# harp_syringe_pump_v1_1.net
KiCad netlist of a schematic drawn in EAGLE
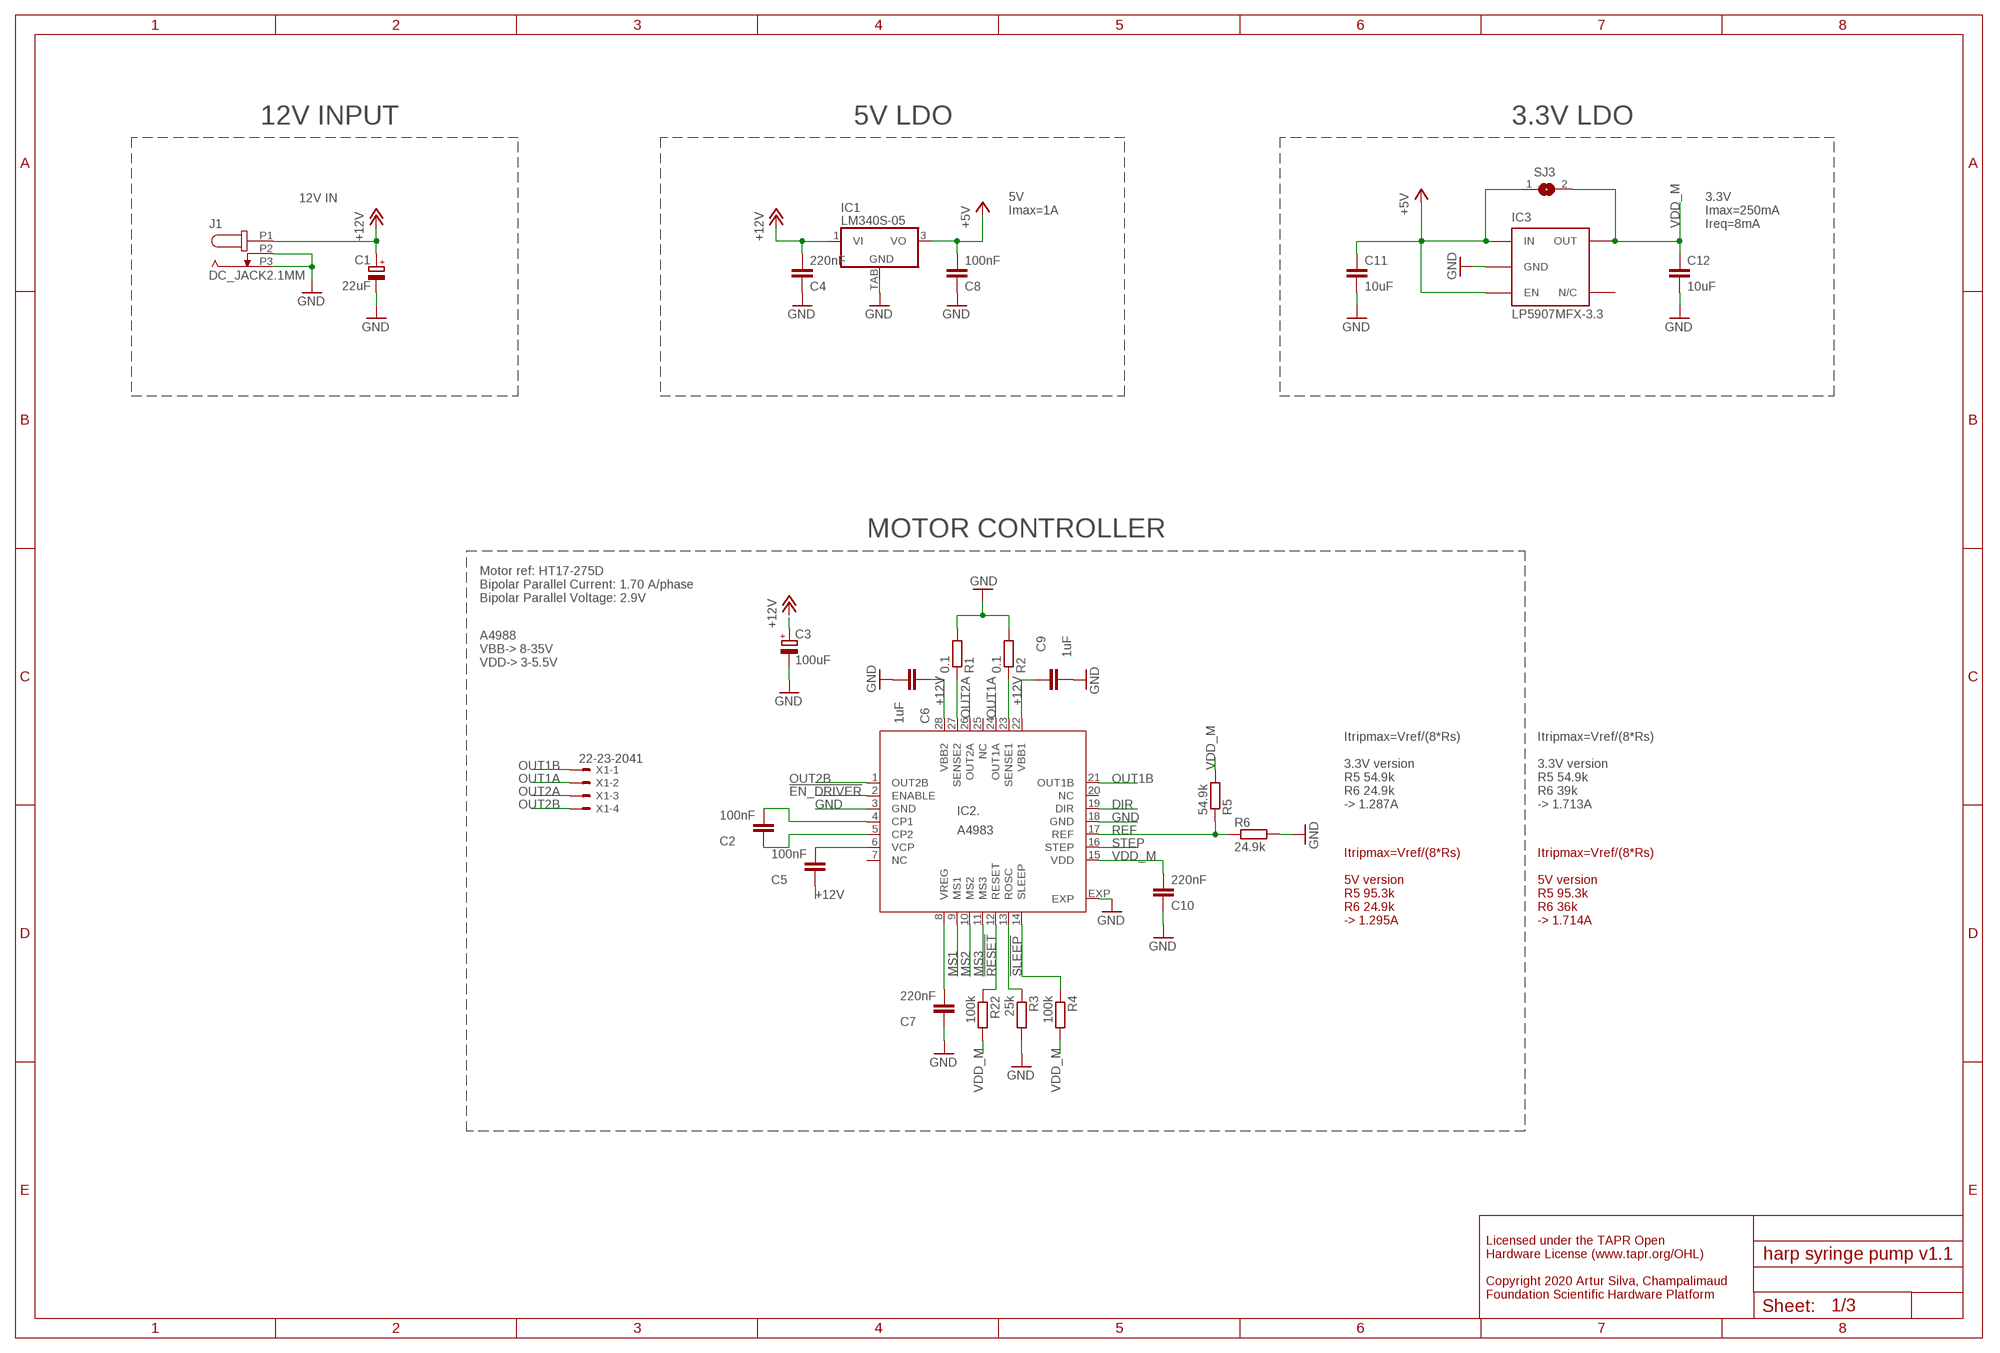
[diagram p0: schematic, sheet 1]
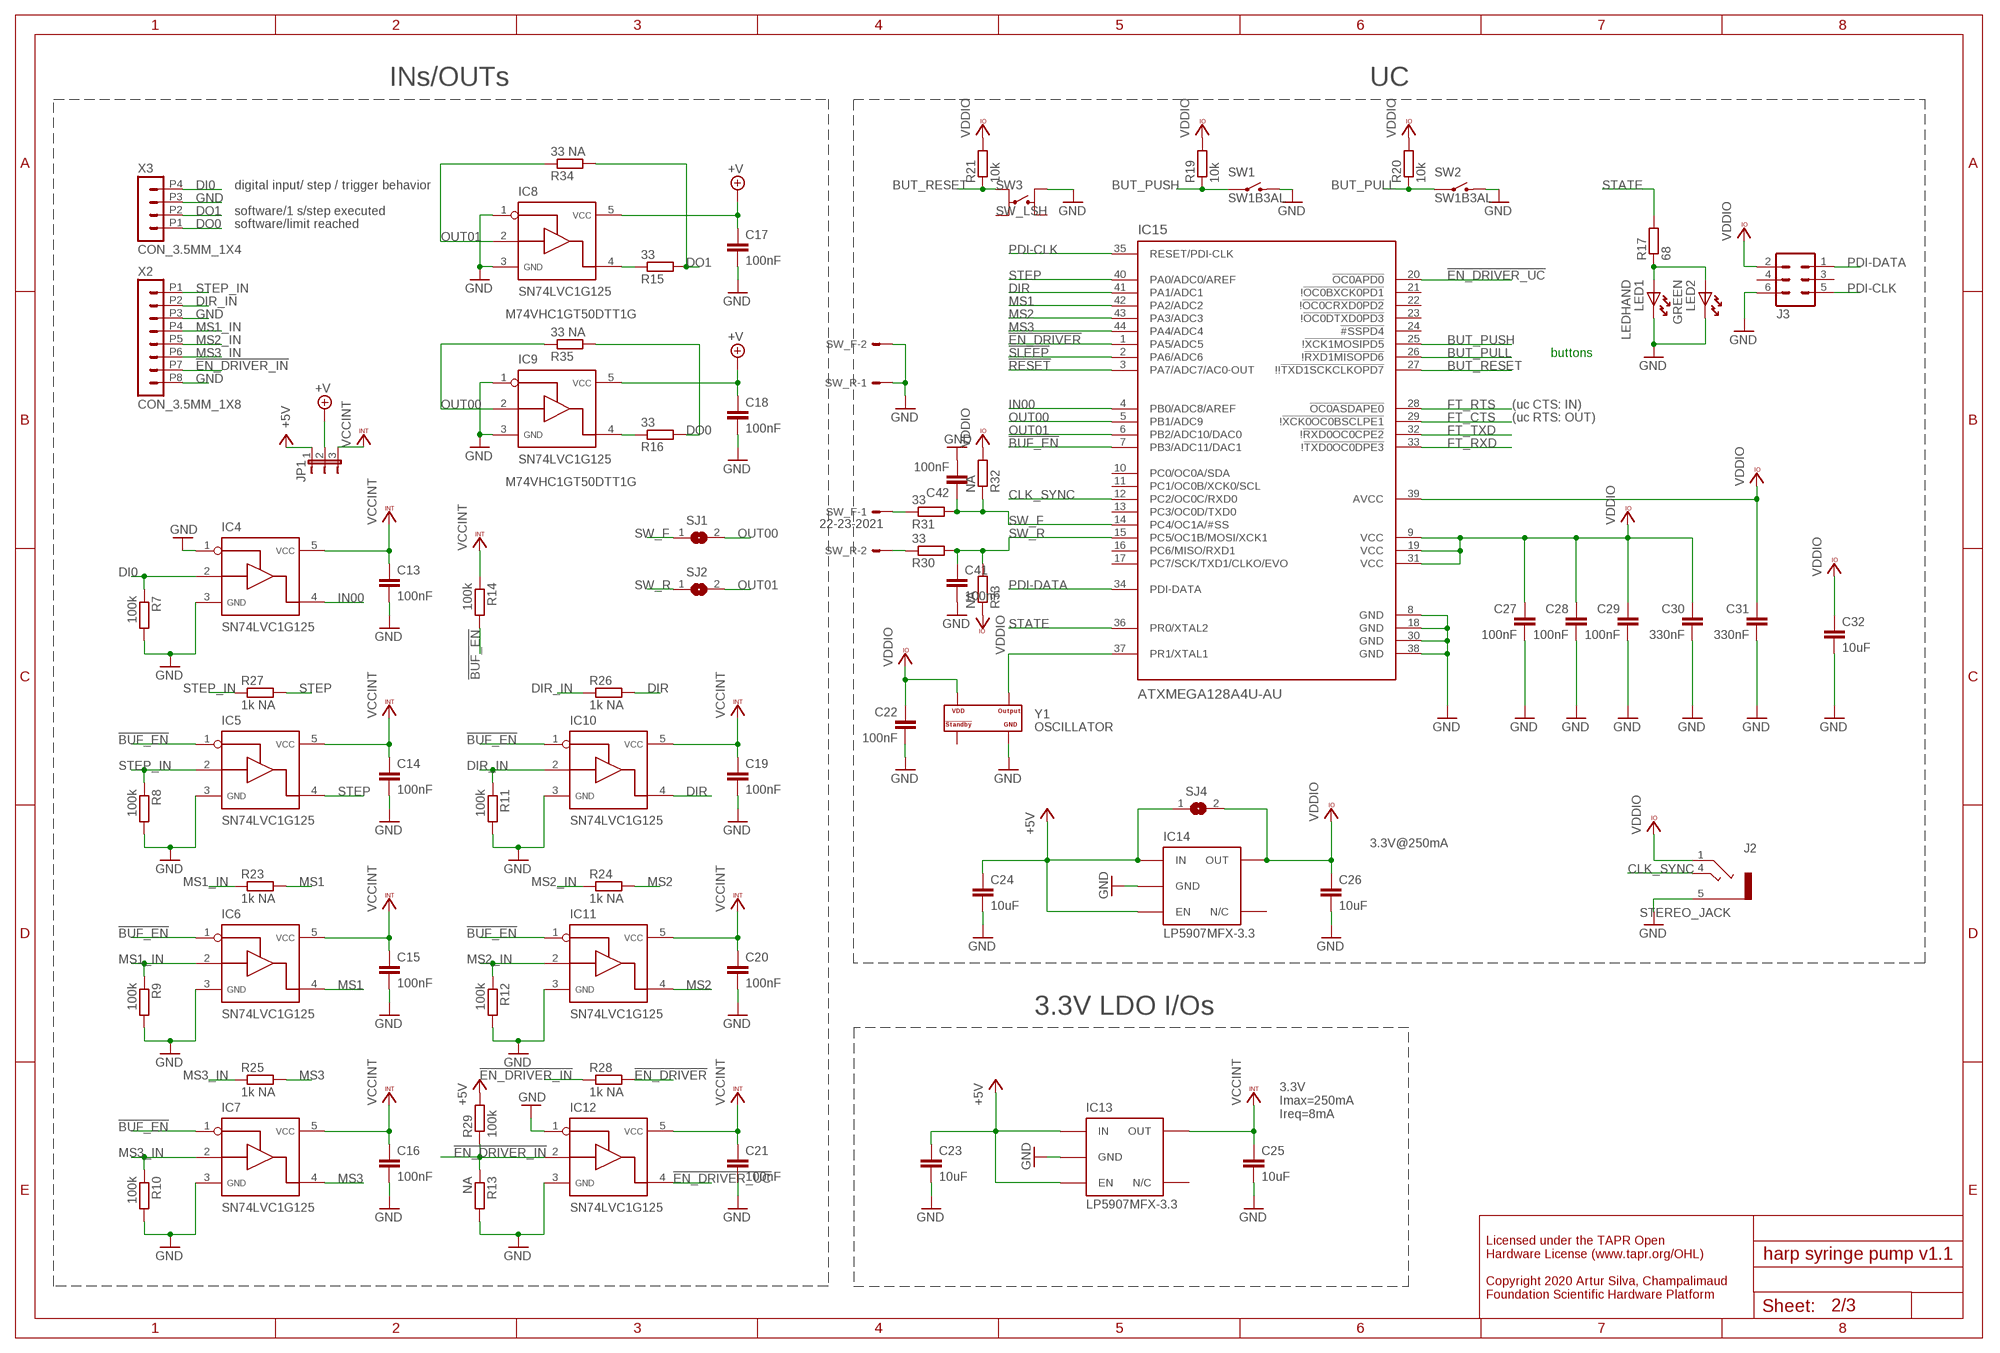
[diagram p1: schematic, sheet 2]
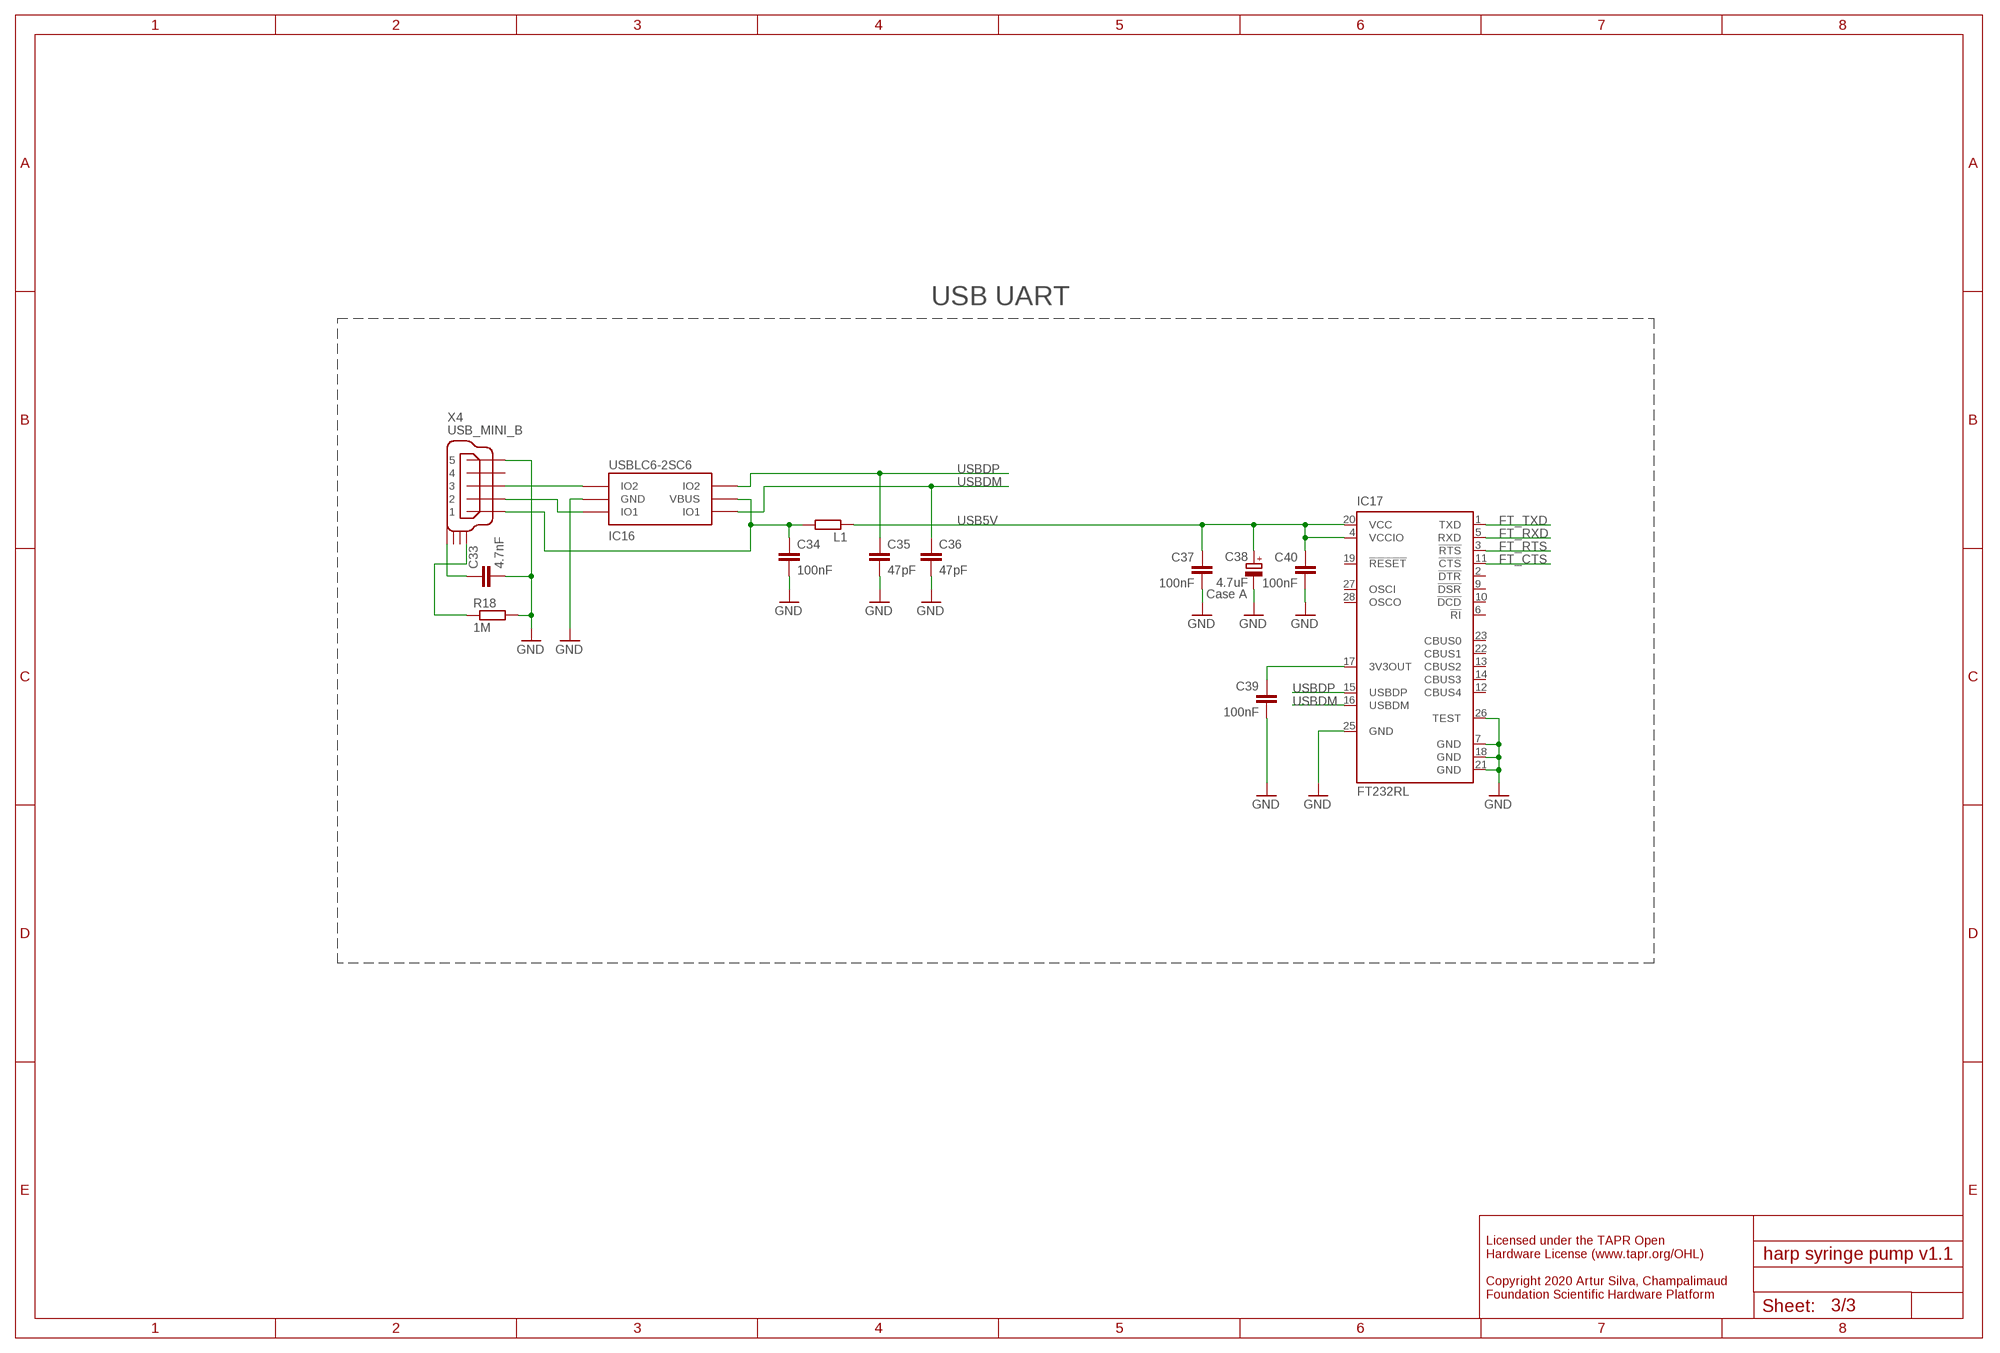
[diagram p2: schematic, sheet 3]

(export (version "E")
  (design (tool "Eeschema 10.0.6"))
  (components
    (comp (ref "C1")
      (value "22uF")
      (footprint "eagle-import:CAP_100UF_HAND")
      (libsource (lib "eagle-import") (part "CAP_100UFHAND"))
    )
    (comp (ref "C2")
      (value "100nF")
      (footprint "eagle-import:C0603")
      (libsource (lib "eagle-import") (part "C-EUC0603"))
    )
    (comp (ref "C3")
      (value "100uF")
      (footprint "eagle-import:PANASONIC_E")
      (libsource (lib "eagle-import") (part "CPOL-EUE"))
    )
    (comp (ref "C4")
      (value "220nF")
      (footprint "eagle-import:C0603")
      (libsource (lib "eagle-import") (part "C-EUC0603"))
    )
    (comp (ref "C5")
      (value "100nF")
      (footprint "eagle-import:C0603")
      (libsource (lib "eagle-import") (part "C-EUC0603"))
    )
    (comp (ref "C6")
      (value "1uF")
      (footprint "eagle-import:C0603")
      (libsource (lib "eagle-import") (part "C-EUC0603"))
    )
    (comp (ref "C7")
      (value "220nF")
      (footprint "eagle-import:C0603")
      (libsource (lib "eagle-import") (part "C-EUC0603"))
    )
    (comp (ref "C8")
      (value "100nF")
      (footprint "eagle-import:C0402")
      (libsource (lib "eagle-import") (part "C-EUC0402"))
    )
    (comp (ref "C9")
      (value "1uF")
      (footprint "eagle-import:C0603")
      (libsource (lib "eagle-import") (part "C-EUC0603"))
    )
    (comp (ref "C10")
      (value "220nF")
      (footprint "eagle-import:C0603")
      (libsource (lib "eagle-import") (part "C-EUC0603"))
    )
    (comp (ref "C11")
      (value "10uF")
      (footprint "eagle-import:C0603")
      (libsource (lib "eagle-import") (part "C-EUC0603"))
    )
    (comp (ref "C12")
      (value "10uF")
      (footprint "eagle-import:C0603")
      (libsource (lib "eagle-import") (part "C-EUC0603"))
    )
    (comp (ref "IC1")
      (value "LM340S-05")
      (footprint "eagle-import:TO263-3")
      (libsource (lib "eagle-import") (part "LM340?-S05"))
    )
    (comp (ref "IC2.")
      (value "A4983")
      (footprint "eagle-import:QFN28ET")
      (fields (field (name "MPN") "A4983SETTR-T"))
      (libsource (lib "eagle-import") (part "A4983"))
    )
    (comp (ref "IC3")
      (value "LP5907MFX-3.3")
      (footprint "eagle-import:TSOT23-5")
      (libsource (lib "eagle-import") (part "TLV700XX"))
    )
    (comp (ref "J1")
      (value "DC_JACK2.1MM")
      (footprint "eagle-import:DC_POWER_INPUT_2.1MM")
      (libsource (lib "eagle-import") (part "DC_JACK2.1MM"))
    )
    (comp (ref "R1")
      (value "0.1")
      (footprint "eagle-import:R2010")
      (libsource (lib "eagle-import") (part "R-EU_R2010"))
    )
    (comp (ref "R2")
      (value "0.1")
      (footprint "eagle-import:R2010")
      (libsource (lib "eagle-import") (part "R-EU_R2010"))
    )
    (comp (ref "R3")
      (value "25k")
      (footprint "eagle-import:R0402")
      (libsource (lib "eagle-import") (part "R-EU_R0402"))
    )
    (comp (ref "R4")
      (value "100k")
      (footprint "eagle-import:R0402")
      (libsource (lib "eagle-import") (part "R-EU_R0402"))
    )
    (comp (ref "R5")
      (value "54.9k")
      (footprint "eagle-import:R0402")
      (libsource (lib "eagle-import") (part "R-EU_R0402"))
    )
    (comp (ref "R6")
      (value "24.9k")
      (footprint "eagle-import:R0402")
      (libsource (lib "eagle-import") (part "R-EU_R0402"))
    )
    (comp (ref "R22")
      (value "100k")
      (footprint "eagle-import:R0402")
      (libsource (lib "eagle-import") (part "R-EU_R0402"))
    )
    (comp (ref "SJ3") (value "SJ") (footprint "eagle-import:SJ") (libsource (lib "eagle-import") (part "SJ")))
    (comp (ref "X1")
      (value "22-23-2041")
      (footprint "eagle-import:22-23-2041")
      (fields (field (name "MF") "MOLEX"))
      (libsource (lib "eagle-import") (part "22-23-2041"))
    )
    (comp (ref "C13")
      (value "100nF")
      (footprint "eagle-import:C0402")
      (libsource (lib "eagle-import") (part "C-EUC0402"))
    )
    (comp (ref "C14")
      (value "100nF")
      (footprint "eagle-import:C0402")
      (libsource (lib "eagle-import") (part "C-EUC0402"))
    )
    (comp (ref "C15")
      (value "100nF")
      (footprint "eagle-import:C0402")
      (libsource (lib "eagle-import") (part "C-EUC0402"))
    )
    (comp (ref "C16")
      (value "100nF")
      (footprint "eagle-import:C0402")
      (libsource (lib "eagle-import") (part "C-EUC0402"))
    )
    (comp (ref "C17")
      (value "100nF")
      (footprint "eagle-import:C0402")
      (libsource (lib "eagle-import") (part "C-EUC0402"))
    )
    (comp (ref "C18")
      (value "100nF")
      (footprint "eagle-import:C0402")
      (libsource (lib "eagle-import") (part "C-EUC0402"))
    )
    (comp (ref "C19")
      (value "100nF")
      (footprint "eagle-import:C0402")
      (libsource (lib "eagle-import") (part "C-EUC0402"))
    )
    (comp (ref "C20")
      (value "100nF")
      (footprint "eagle-import:C0402")
      (libsource (lib "eagle-import") (part "C-EUC0402"))
    )
    (comp (ref "C21")
      (value "100nF")
      (footprint "eagle-import:C0402")
      (libsource (lib "eagle-import") (part "C-EUC0402"))
    )
    (comp (ref "C22")
      (value "100nF")
      (footprint "eagle-import:C0402")
      (libsource (lib "eagle-import") (part "C-EUC0402"))
    )
    (comp (ref "C23")
      (value "10uF")
      (footprint "eagle-import:C0603")
      (libsource (lib "eagle-import") (part "C-EUC0603"))
    )
    (comp (ref "C24")
      (value "10uF")
      (footprint "eagle-import:C0603")
      (libsource (lib "eagle-import") (part "C-EUC0603"))
    )
    (comp (ref "C25")
      (value "10uF")
      (footprint "eagle-import:C0603")
      (libsource (lib "eagle-import") (part "C-EUC0603"))
    )
    (comp (ref "C26")
      (value "10uF")
      (footprint "eagle-import:C0603")
      (libsource (lib "eagle-import") (part "C-EUC0603"))
    )
    (comp (ref "C27")
      (value "100nF")
      (footprint "eagle-import:C0402")
      (libsource (lib "eagle-import") (part "C-EUC0402"))
    )
    (comp (ref "C28")
      (value "100nF")
      (footprint "eagle-import:C0402")
      (libsource (lib "eagle-import") (part "C-EUC0402"))
    )
    (comp (ref "C29")
      (value "100nF")
      (footprint "eagle-import:C0402")
      (libsource (lib "eagle-import") (part "C-EUC0402"))
    )
    (comp (ref "C30")
      (value "330nF")
      (footprint "eagle-import:C0402")
      (libsource (lib "eagle-import") (part "C-EUC0402"))
    )
    (comp (ref "C31")
      (value "330nF")
      (footprint "eagle-import:C0402")
      (libsource (lib "eagle-import") (part "C-EUC0402"))
    )
    (comp (ref "C32")
      (value "10uF")
      (footprint "eagle-import:C0603")
      (libsource (lib "eagle-import") (part "C-EUC0603"))
    )
    (comp (ref "C41")
      (value "100nF")
      (footprint "eagle-import:C0402")
      (libsource (lib "eagle-import") (part "C-EUC0402"))
    )
    (comp (ref "C42")
      (value "100nF")
      (footprint "eagle-import:C0402")
      (libsource (lib "eagle-import") (part "C-EUC0402"))
    )
    (comp (ref "IC4")
      (value "SN74LVC1G125")
      (footprint "eagle-import:SOT23-5")
      (libsource (lib "eagle-import") (part "SN74LVC1G125"))
    )
    (comp (ref "IC5")
      (value "SN74LVC1G125")
      (footprint "eagle-import:SOT23-5")
      (libsource (lib "eagle-import") (part "SN74LVC1G125"))
    )
    (comp (ref "IC6")
      (value "SN74LVC1G125")
      (footprint "eagle-import:SOT23-5")
      (libsource (lib "eagle-import") (part "SN74LVC1G125"))
    )
    (comp (ref "IC7")
      (value "SN74LVC1G125")
      (footprint "eagle-import:SOT23-5")
      (libsource (lib "eagle-import") (part "SN74LVC1G125"))
    )
    (comp (ref "IC8")
      (value "SN74LVC1G125")
      (footprint "eagle-import:SOT23-5")
      (libsource (lib "eagle-import") (part "SN74LVC1G125"))
    )
    (comp (ref "IC9")
      (value "SN74LVC1G125")
      (footprint "eagle-import:SOT23-5")
      (libsource (lib "eagle-import") (part "SN74LVC1G125"))
    )
    (comp (ref "IC10")
      (value "SN74LVC1G125")
      (footprint "eagle-import:SOT23-5")
      (libsource (lib "eagle-import") (part "SN74LVC1G125"))
    )
    (comp (ref "IC11")
      (value "SN74LVC1G125")
      (footprint "eagle-import:SOT23-5")
      (libsource (lib "eagle-import") (part "SN74LVC1G125"))
    )
    (comp (ref "IC12")
      (value "SN74LVC1G125")
      (footprint "eagle-import:SOT23-5")
      (libsource (lib "eagle-import") (part "SN74LVC1G125"))
    )
    (comp (ref "IC13")
      (value "LP5907MFX-3.3")
      (footprint "eagle-import:TSOT23-5")
      (libsource (lib "eagle-import") (part "TLV700XX"))
    )
    (comp (ref "IC14")
      (value "LP5907MFX-3.3")
      (footprint "eagle-import:TSOT23-5")
      (libsource (lib "eagle-import") (part "TLV700XX"))
    )
    (comp (ref "IC15")
      (value "ATXMEGA128A4U-AU")
      (footprint "eagle-import:QFP80P1200X1200X120-44N")
      (libsource (lib "eagle-import") (part "AT-XMEGA-XXA4-AU"))
    )
    (comp (ref "J2")
      (value "STEREO_JACK")
      (footprint "eagle-import:35RASMT2BHNTRX")
      (libsource (lib "eagle-import") (part "STEREO_JACK"))
    )
    (comp (ref "J3")
      (value "MA03-2")
      (footprint "eagle-import:MA03-2")
      (libsource (lib "eagle-import") (part "MA03-2"))
    )
    (comp (ref "JP1")
      (value "JP2E")
      (footprint "eagle-import:JP2")
      (libsource (lib "eagle-import") (part "JP2E"))
    )
    (comp (ref "LED1")
      (value "LEDHAND")
      (footprint "eagle-import:LED_HAND")
      (libsource (lib "eagle-import") (part "LEDHAND"))
    )
    (comp (ref "LED2")
      (value "GREEN")
      (footprint "eagle-import:LED_HAND")
      (libsource (lib "eagle-import") (part "LEDHAND"))
    )
    (comp (ref "R7")
      (value "100k")
      (footprint "eagle-import:R0402")
      (libsource (lib "eagle-import") (part "R-EU_R0402"))
    )
    (comp (ref "R8")
      (value "100k")
      (footprint "eagle-import:R0402")
      (libsource (lib "eagle-import") (part "R-EU_R0402"))
    )
    (comp (ref "R9")
      (value "100k")
      (footprint "eagle-import:R0402")
      (libsource (lib "eagle-import") (part "R-EU_R0402"))
    )
    (comp (ref "R10")
      (value "100k")
      (footprint "eagle-import:R0402")
      (libsource (lib "eagle-import") (part "R-EU_R0402"))
    )
    (comp (ref "R11")
      (value "100k")
      (footprint "eagle-import:R0402")
      (libsource (lib "eagle-import") (part "R-EU_R0402"))
    )
    (comp (ref "R12")
      (value "100k")
      (footprint "eagle-import:R0402")
      (libsource (lib "eagle-import") (part "R-EU_R0402"))
    )
    (comp (ref "R13")
      (value "NA")
      (footprint "eagle-import:R0402")
      (libsource (lib "eagle-import") (part "R-EU_R0402"))
    )
    (comp (ref "R14")
      (value "100k")
      (footprint "eagle-import:R0402")
      (libsource (lib "eagle-import") (part "R-EU_R0402"))
    )
    (comp (ref "R15")
      (value "33")
      (footprint "eagle-import:R0402")
      (libsource (lib "eagle-import") (part "R-EU_R0402"))
    )
    (comp (ref "R16")
      (value "33")
      (footprint "eagle-import:R0402")
      (libsource (lib "eagle-import") (part "R-EU_R0402"))
    )
    (comp (ref "R17")
      (value "68")
      (footprint "eagle-import:R0402")
      (libsource (lib "eagle-import") (part "R-EU_R0402"))
    )
    (comp (ref "R19")
      (value "10k")
      (footprint "eagle-import:R0402")
      (libsource (lib "eagle-import") (part "R-EU_R0402"))
    )
    (comp (ref "R20")
      (value "10k")
      (footprint "eagle-import:R0402")
      (libsource (lib "eagle-import") (part "R-EU_R0402"))
    )
    (comp (ref "R21")
      (value "10k")
      (footprint "eagle-import:R0402")
      (libsource (lib "eagle-import") (part "R-EU_R0402"))
    )
    (comp (ref "R23")
      (value "1k NA")
      (footprint "eagle-import:R0402")
      (libsource (lib "eagle-import") (part "R-EU_R0402"))
    )
    (comp (ref "R24")
      (value "1k NA")
      (footprint "eagle-import:R0402")
      (libsource (lib "eagle-import") (part "R-EU_R0402"))
    )
    (comp (ref "R25")
      (value "1k NA")
      (footprint "eagle-import:R0402")
      (libsource (lib "eagle-import") (part "R-EU_R0402"))
    )
    (comp (ref "R26")
      (value "1k NA")
      (footprint "eagle-import:R0402")
      (libsource (lib "eagle-import") (part "R-EU_R0402"))
    )
    (comp (ref "R27")
      (value "1k NA")
      (footprint "eagle-import:R0402")
      (libsource (lib "eagle-import") (part "R-EU_R0402"))
    )
    (comp (ref "R28")
      (value "1k NA")
      (footprint "eagle-import:R0402")
      (libsource (lib "eagle-import") (part "R-EU_R0402"))
    )
    (comp (ref "R29")
      (value "100k")
      (footprint "eagle-import:R0402")
      (libsource (lib "eagle-import") (part "R-EU_R0402"))
    )
    (comp (ref "R30")
      (value "33")
      (footprint "eagle-import:R0402")
      (libsource (lib "eagle-import") (part "R-EU_R0402"))
    )
    (comp (ref "R31")
      (value "33")
      (footprint "eagle-import:R0402")
      (libsource (lib "eagle-import") (part "R-EU_R0402"))
    )
    (comp (ref "R32")
      (value "NA")
      (footprint "eagle-import:R0402")
      (libsource (lib "eagle-import") (part "R-EU_R0402"))
    )
    (comp (ref "R33")
      (value "NA")
      (footprint "eagle-import:R0402")
      (libsource (lib "eagle-import") (part "R-EU_R0402"))
    )
    (comp (ref "R34")
      (value "33 NA")
      (footprint "eagle-import:R0402")
      (libsource (lib "eagle-import") (part "R-EU_R0402"))
    )
    (comp (ref "R35")
      (value "33 NA")
      (footprint "eagle-import:R0402")
      (libsource (lib "eagle-import") (part "R-EU_R0402"))
    )
    (comp (ref "SJ1") (value "SJ") (footprint "eagle-import:SJ") (libsource (lib "eagle-import") (part "SJ")))
    (comp (ref "SJ2") (value "SJ") (footprint "eagle-import:SJ") (libsource (lib "eagle-import") (part "SJ")))
    (comp (ref "SJ4") (value "SJ") (footprint "eagle-import:SJ") (libsource (lib "eagle-import") (part "SJ")))
    (comp (ref "SW1")
      (value "SW1B3AL")
      (footprint "eagle-import:SW_B3AL")
      (libsource (lib "eagle-import") (part "SW1B3AL"))
    )
    (comp (ref "SW2")
      (value "SW1B3AL")
      (footprint "eagle-import:SW_B3AL")
      (libsource (lib "eagle-import") (part "SW1B3AL"))
    )
    (comp (ref "SW3")
      (value "SW_LSH")
      (footprint "eagle-import:SWITCH_LSH")
      (libsource (lib "eagle-import") (part "SW_LSH"))
    )
    (comp (ref "SW_F")
      (value "22-23-2021")
      (footprint "eagle-import:22-23-2021")
      (fields (field (name "MF") "MOLEX"))
      (libsource (lib "eagle-import") (part "22-23-2021"))
    )
    (comp (ref "SW_R")
      (value "22-23-2021")
      (footprint "eagle-import:22-23-2021")
      (fields (field (name "MF") "MOLEX"))
      (libsource (lib "eagle-import") (part "22-23-2021"))
    )
    (comp (ref "X2")
      (value "CON_3.5MM_1X8")
      (footprint "eagle-import:CON_3.5MM_1X8")
      (libsource (lib "eagle-import") (part "CON_3.5MM_1X8"))
    )
    (comp (ref "X3")
      (value "CON_3.5MM_1X4")
      (footprint "eagle-import:CON_3.5MM_1X4")
      (libsource (lib "eagle-import") (part "CON_3.5MM_1X4"))
    )
    (comp (ref "Y1")
      (value "OSCILLATOR")
      (footprint "eagle-import:OSCILLATOR_3.2X2.5")
      (libsource (lib "eagle-import") (part "OSCILLATOR"))
    )
    (comp (ref "C33")
      (value "4.7nF")
      (footprint "eagle-import:C0402")
      (libsource (lib "eagle-import") (part "C-EUC0402"))
    )
    (comp (ref "C34")
      (value "100nF")
      (footprint "eagle-import:C0402")
      (libsource (lib "eagle-import") (part "C-EUC0402"))
    )
    (comp (ref "C35")
      (value "47pF")
      (footprint "eagle-import:C0402")
      (libsource (lib "eagle-import") (part "C-EUC0402"))
    )
    (comp (ref "C36")
      (value "47pF")
      (footprint "eagle-import:C0402")
      (libsource (lib "eagle-import") (part "C-EUC0402"))
    )
    (comp (ref "C37")
      (value "100nF")
      (footprint "eagle-import:C0402")
      (libsource (lib "eagle-import") (part "C-EUC0402"))
    )
    (comp (ref "C38")
      (value "4.7uF")
      (footprint "eagle-import:A_3216-18W")
      (libsource (lib "eagle-import") (part "CPOL-EUA/3216-18W"))
    )
    (comp (ref "C39")
      (value "100nF")
      (footprint "eagle-import:C0402")
      (libsource (lib "eagle-import") (part "C-EUC0402"))
    )
    (comp (ref "C40")
      (value "100nF")
      (footprint "eagle-import:C0402")
      (libsource (lib "eagle-import") (part "C-EUC0402"))
    )
    (comp (ref "IC16")
      (value "USBLC6-2SC6")
      (footprint "eagle-import:SOT23-6L")
      (libsource (lib "eagle-import") (part "USBLC6-2"))
    )
    (comp (ref "IC17")
      (value "FT232RL")
      (footprint "eagle-import:SSOP28")
      (libsource (lib "eagle-import") (part "FT232RL"))
    )
    (comp (ref "L1")
      (value "???")
      (footprint "eagle-import:R0805")
      (libsource (lib "eagle-import") (part "R-EU_R0805"))
    )
    (comp (ref "R18")
      (value "1M")
      (footprint "eagle-import:R0402")
      (libsource (lib "eagle-import") (part "R-EU_R0402"))
    )
    (comp (ref "X4")
      (value "USB_MINI_B")
      (footprint "eagle-import:240-0002-1")
      (libsource (lib "eagle-import") (part "USB_MINI_B"))
    )
  )
  (nets
    (net (code "1") (name "+5V") (class "Default")
      (node (ref "C11") (pin "1") (pinfunction "1_1") (pintype "passive"))
      (node (ref "C23") (pin "1") (pinfunction "1_1") (pintype "passive"))
      (node (ref "C24") (pin "1") (pinfunction "1_1") (pintype "passive"))
      (node (ref "C8") (pin "2") (pinfunction "2_2") (pintype "passive"))
      (node (ref "IC1") (pin "3") (pinfunction "VO_3") (pintype "passive"))
      (node (ref "IC13") (pin "1") (pinfunction "IN_1") (pintype "bidirectional"))
      (node (ref "IC13") (pin "3") (pinfunction "EN_3") (pintype "bidirectional"))
      (node (ref "IC14") (pin "1") (pinfunction "IN_1") (pintype "bidirectional"))
      (node (ref "IC14") (pin "3") (pinfunction "EN_3") (pintype "bidirectional"))
      (node (ref "IC3") (pin "1") (pinfunction "IN_1") (pintype "bidirectional"))
      (node (ref "IC3") (pin "3") (pinfunction "EN_3") (pintype "bidirectional"))
      (node (ref "JP1") (pin "1") (pinfunction "1_1") (pintype "passive"))
      (node (ref "R29") (pin "2") (pinfunction "2_2") (pintype "passive"))
      (node (ref "SJ3") (pin "1") (pinfunction "1_1") (pintype "passive"))
      (node (ref "SJ4") (pin "1") (pinfunction "1_1") (pintype "passive"))
    )
    (net (code "2") (name "+12V") (class "Default")
      (node (ref "C1") (pin "+") (pinfunction "+_+") (pintype "passive"))
      (node (ref "C3") (pin "+") (pinfunction "+_+") (pintype "passive"))
      (node (ref "C4") (pin "2") (pinfunction "2_2") (pintype "passive"))
      (node (ref "C5") (pin "1") (pinfunction "1_1") (pintype "passive"))
      (node (ref "C6") (pin "1") (pinfunction "1_1") (pintype "passive"))
      (node (ref "C9") (pin "1") (pinfunction "1_1") (pintype "passive"))
      (node (ref "IC1") (pin "1") (pinfunction "VI_1") (pintype "input"))
      (node (ref "IC2.") (pin "22") (pinfunction "VBB1_22") (pintype "power_in"))
      (node (ref "IC2.") (pin "28") (pinfunction "VBB2_28") (pintype "power_in"))
      (node (ref "J1") (pin "P1") (pinfunction "1_P1") (pintype "passive"))
    )
    (net (code "3") (name "+V") (class "Default")
      (node (ref "C17") (pin "1") (pinfunction "1_1") (pintype "passive"))
      (node (ref "C18") (pin "1") (pinfunction "1_1") (pintype "passive"))
      (node (ref "IC8") (pin "5") (pinfunction "P$5_5") (pintype "bidirectional"))
      (node (ref "IC9") (pin "5") (pinfunction "P$5_5") (pintype "bidirectional"))
      (node (ref "JP1") (pin "2") (pinfunction "2_2") (pintype "passive"))
    )
    (net (code "4") (name "BUT_PULL") (class "Default")
      (node (ref "IC15") (pin "26") (pinfunction "~RXD1MISOPD6_26") (pintype "bidirectional"))
      (node (ref "R20") (pin "1") (pinfunction "1_1") (pintype "passive"))
      (node (ref "SW2") (pin "P") (pinfunction "P_P") (pintype "passive"))
    )
    (net (code "5") (name "BUT_PUSH") (class "Default")
      (node (ref "IC15") (pin "25") (pinfunction "~XCK1MOSIPD5_25") (pintype "bidirectional"))
      (node (ref "R19") (pin "1") (pinfunction "1_1") (pintype "passive"))
      (node (ref "SW1") (pin "P") (pinfunction "P_P") (pintype "passive"))
    )
    (net (code "6") (name "BUT_RESET") (class "Default")
      (node (ref "IC15") (pin "27") (pinfunction "~~{TXD1SCKCLKOPD7}_27") (pintype "bidirectional"))
      (node (ref "R21") (pin "1") (pinfunction "1_1") (pintype "passive"))
      (node (ref "SW3") (pin "P0") (pinfunction "P_P0") (pintype "passive"))
    )
    (net (code "7") (name "CLK_SYNC") (class "Default")
      (node (ref "IC15") (pin "12") (pinfunction "PC2/OC0C/RXD0_12") (pintype "bidirectional"))
      (node (ref "J2") (pin "4") (pinfunction "4_4") (pintype "passive"))
    )
    (net (code "8") (name "DI0") (class "Default")
      (node (ref "IC4") (pin "2") (pinfunction "P$2_2") (pintype "bidirectional"))
      (node (ref "R7") (pin "1") (pinfunction "1_1") (pintype "passive"))
      (node (ref "X3") (pin "P4") (pinfunction "4_P4") (pintype "passive"))
    )
    (net (code "9") (name "DIR") (class "Default")
      (node (ref "IC10") (pin "4") (pinfunction "P$4_4") (pintype "bidirectional"))
      (node (ref "IC15") (pin "41") (pinfunction "PA1/ADC1_41") (pintype "bidirectional"))
      (node (ref "IC2.") (pin "19") (pinfunction "DIR_19") (pintype "input"))
      (node (ref "R26") (pin "2") (pinfunction "2_2") (pintype "passive"))
    )
    (net (code "10") (name "DIR_IN") (class "Default")
      (node (ref "IC10") (pin "2") (pinfunction "P$2_2") (pintype "bidirectional"))
      (node (ref "R11") (pin "1") (pinfunction "1_1") (pintype "passive"))
      (node (ref "R26") (pin "1") (pinfunction "1_1") (pintype "passive"))
      (node (ref "X2") (pin "P2") (pinfunction "2_P2") (pintype "passive"))
    )
    (net (code "11") (name "DO0") (class "Default")
      (node (ref "R16") (pin "2") (pinfunction "2_2") (pintype "passive"))
      (node (ref "R35") (pin "2") (pinfunction "2_2") (pintype "passive"))
      (node (ref "X3") (pin "P1") (pinfunction "1_P1") (pintype "passive"))
    )
    (net (code "12") (name "DO1") (class "Default")
      (node (ref "R15") (pin "2") (pinfunction "2_2") (pintype "passive"))
      (node (ref "R34") (pin "2") (pinfunction "2_2") (pintype "passive"))
      (node (ref "X3") (pin "P2") (pinfunction "2_P2") (pintype "passive"))
    )
    (net (code "13") (name "FT_CTS") (class "Default")
      (node (ref "IC15") (pin "29") (pinfunction "~XCK0OC0BSCLPE1_29") (pintype "bidirectional"))
      (node (ref "IC17") (pin "11") (pinfunction "~{CTS}_11") (pintype "input"))
    )
    (net (code "14") (name "FT_RTS") (class "Default")
      (node (ref "IC15") (pin "28") (pinfunction "~{OC0ASDAPE0}_28") (pintype "bidirectional"))
      (node (ref "IC17") (pin "3") (pinfunction "~{RTS}_3") (pintype "output"))
    )
    (net (code "15") (name "FT_RXD") (class "Default")
      (node (ref "IC15") (pin "33") (pinfunction "~TXD0OC0DPE3_33") (pintype "bidirectional"))
      (node (ref "IC17") (pin "5") (pinfunction "RXD_5") (pintype "input"))
    )
    (net (code "16") (name "FT_TXD") (class "Default")
      (node (ref "IC15") (pin "32") (pinfunction "~RXD0OC0CPE2_32") (pintype "bidirectional"))
      (node (ref "IC17") (pin "1") (pinfunction "TXD_1") (pintype "output"))
    )
    (net (code "17") (name "GND") (class "Default")
      (node (ref "C1") (pin "-") (pinfunction "-_-") (pintype "passive"))
      (node (ref "C10") (pin "1") (pinfunction "1_1") (pintype "passive"))
      (node (ref "C11") (pin "2") (pinfunction "2_2") (pintype "passive"))
      (node (ref "C12") (pin "2") (pinfunction "2_2") (pintype "passive"))
      (node (ref "C13") (pin "2") (pinfunction "2_2") (pintype "passive"))
      (node (ref "C14") (pin "2") (pinfunction "2_2") (pintype "passive"))
      (node (ref "C15") (pin "2") (pinfunction "2_2") (pintype "passive"))
      (node (ref "C16") (pin "2") (pinfunction "2_2") (pintype "passive"))
      (node (ref "C17") (pin "2") (pinfunction "2_2") (pintype "passive"))
      (node (ref "C18") (pin "2") (pinfunction "2_2") (pintype "passive"))
      (node (ref "C19") (pin "2") (pinfunction "2_2") (pintype "passive"))
      (node (ref "C20") (pin "2") (pinfunction "2_2") (pintype "passive"))
      (node (ref "C21") (pin "2") (pinfunction "2_2") (pintype "passive"))
      (node (ref "C22") (pin "2") (pinfunction "2_2") (pintype "passive"))
      (node (ref "C23") (pin "2") (pinfunction "2_2") (pintype "passive"))
      (node (ref "C24") (pin "2") (pinfunction "2_2") (pintype "passive"))
      (node (ref "C25") (pin "2") (pinfunction "2_2") (pintype "passive"))
      (node (ref "C26") (pin "2") (pinfunction "2_2") (pintype "passive"))
      (node (ref "C27") (pin "2") (pinfunction "2_2") (pintype "passive"))
      (node (ref "C28") (pin "2") (pinfunction "2_2") (pintype "passive"))
      (node (ref "C29") (pin "2") (pinfunction "2_2") (pintype "passive"))
      (node (ref "C3") (pin "-") (pinfunction "-_-") (pintype "passive"))
      (node (ref "C30") (pin "2") (pinfunction "2_2") (pintype "passive"))
      (node (ref "C31") (pin "2") (pinfunction "2_2") (pintype "passive"))
      (node (ref "C32") (pin "2") (pinfunction "2_2") (pintype "passive"))
      (node (ref "C33") (pin "2") (pinfunction "2_2") (pintype "passive"))
      (node (ref "C34") (pin "2") (pinfunction "2_2") (pintype "passive"))
      (node (ref "C35") (pin "2") (pinfunction "2_2") (pintype "passive"))
      (node (ref "C36") (pin "2") (pinfunction "2_2") (pintype "passive"))
      (node (ref "C37") (pin "2") (pinfunction "2_2") (pintype "passive"))
      (node (ref "C38") (pin "-") (pinfunction "-_-") (pintype "passive"))
      (node (ref "C39") (pin "2") (pinfunction "2_2") (pintype "passive"))
      (node (ref "C4") (pin "1") (pinfunction "1_1") (pintype "passive"))
      (node (ref "C40") (pin "2") (pinfunction "2_2") (pintype "passive"))
      (node (ref "C41") (pin "2") (pinfunction "2_2") (pintype "passive"))
      (node (ref "C42") (pin "2") (pinfunction "2_2") (pintype "passive"))
      (node (ref "C6") (pin "2") (pinfunction "2_2") (pintype "passive"))
      (node (ref "C7") (pin "1") (pinfunction "1_1") (pintype "passive"))
      (node (ref "C8") (pin "1") (pinfunction "1_1") (pintype "passive"))
      (node (ref "C9") (pin "2") (pinfunction "2_2") (pintype "passive"))
      (node (ref "IC1") (pin "TAB") (pinfunction "GND_TAB") (pintype "passive"))
      (node (ref "IC10") (pin "3") (pinfunction "P$3_3") (pintype "bidirectional"))
      (node (ref "IC11") (pin "3") (pinfunction "P$3_3") (pintype "bidirectional"))
      (node (ref "IC12") (pin "1") (pinfunction "P$1_1") (pintype "bidirectional"))
      (node (ref "IC12") (pin "3") (pinfunction "P$3_3") (pintype "bidirectional"))
      (node (ref "IC13") (pin "2") (pinfunction "GND_2") (pintype "bidirectional"))
      (node (ref "IC14") (pin "2") (pinfunction "GND_2") (pintype "bidirectional"))
      (node (ref "IC15") (pin "18") (pinfunction "GND_18") (pintype "power_in"))
      (node (ref "IC15") (pin "30") (pinfunction "GND_30") (pintype "power_in"))
      (node (ref "IC15") (pin "38") (pinfunction "GND_38") (pintype "power_in"))
      (node (ref "IC15") (pin "8") (pinfunction "GND_8") (pintype "power_in"))
      (node (ref "IC16") (pin "P$2") (pinfunction "GND_P$2") (pintype "bidirectional"))
      (node (ref "IC17") (pin "18") (pinfunction "GND_18") (pintype "power_in"))
      (node (ref "IC17") (pin "21") (pinfunction "GND_21") (pintype "power_in"))
      (node (ref "IC17") (pin "25") (pinfunction "GND_25") (pintype "power_in"))
      (node (ref "IC17") (pin "26") (pinfunction "TEST_26") (pintype "input"))
      (node (ref "IC17") (pin "7") (pinfunction "GND_7") (pintype "power_in"))
      (node (ref "IC2.") (pin "18") (pinfunction "GND_18") (pintype "power_in"))
      (node (ref "IC2.") (pin "3") (pinfunction "GND_3") (pintype "power_in"))
      (node (ref "IC2.") (pin "EXP") (pinfunction "EXP_EXP") (pintype "passive"))
      (node (ref "IC3") (pin "2") (pinfunction "GND_2") (pintype "bidirectional"))
      (node (ref "IC4") (pin "1") (pinfunction "P$1_1") (pintype "bidirectional"))
      (node (ref "IC4") (pin "3") (pinfunction "P$3_3") (pintype "bidirectional"))
      (node (ref "IC5") (pin "3") (pinfunction "P$3_3") (pintype "bidirectional"))
      (node (ref "IC6") (pin "3") (pinfunction "P$3_3") (pintype "bidirectional"))
      (node (ref "IC7") (pin "3") (pinfunction "P$3_3") (pintype "bidirectional"))
      (node (ref "IC8") (pin "1") (pinfunction "P$1_1") (pintype "bidirectional"))
      (node (ref "IC8") (pin "3") (pinfunction "P$3_3") (pintype "bidirectional"))
      (node (ref "IC9") (pin "1") (pinfunction "P$1_1") (pintype "bidirectional"))
      (node (ref "IC9") (pin "3") (pinfunction "P$3_3") (pintype "bidirectional"))
      (node (ref "J1") (pin "P2") (pinfunction "2_P2") (pintype "passive"))
      (node (ref "J1") (pin "P3") (pinfunction "3_P3") (pintype "passive"))
      (node (ref "J2") (pin "5") (pinfunction "5_5") (pintype "passive"))
      (node (ref "J3") (pin "6") (pinfunction "6_6") (pintype "passive"))
      (node (ref "LED1") (pin "K") (pinfunction "K_K") (pintype "bidirectional"))
      (node (ref "LED2") (pin "K") (pinfunction "K_K") (pintype "bidirectional"))
      (node (ref "R1") (pin "2") (pinfunction "2_2") (pintype "passive"))
      (node (ref "R10") (pin "2") (pinfunction "2_2") (pintype "passive"))
      (node (ref "R11") (pin "2") (pinfunction "2_2") (pintype "passive"))
      (node (ref "R12") (pin "2") (pinfunction "2_2") (pintype "passive"))
      (node (ref "R13") (pin "2") (pinfunction "2_2") (pintype "passive"))
      (node (ref "R18") (pin "2") (pinfunction "2_2") (pintype "passive"))
      (node (ref "R2") (pin "2") (pinfunction "2_2") (pintype "passive"))
      (node (ref "R3") (pin "2") (pinfunction "2_2") (pintype "passive"))
      (node (ref "R6") (pin "2") (pinfunction "2_2") (pintype "passive"))
      (node (ref "R7") (pin "2") (pinfunction "2_2") (pintype "passive"))
      (node (ref "R8") (pin "2") (pinfunction "2_2") (pintype "passive"))
      (node (ref "R9") (pin "2") (pinfunction "2_2") (pintype "passive"))
      (node (ref "SW1") (pin "O") (pinfunction "O_O") (pintype "passive"))
      (node (ref "SW2") (pin "O") (pinfunction "O_O") (pintype "passive"))
      (node (ref "SW3") (pin "O0") (pinfunction "O_O0") (pintype "passive"))
      (node (ref "SW_F") (pin "2") (pinfunction "S_2") (pintype "passive"))
      (node (ref "SW_R") (pin "1") (pinfunction "S_1") (pintype "passive"))
      (node (ref "X2") (pin "P3") (pinfunction "3_P3") (pintype "passive"))
      (node (ref "X2") (pin "P8") (pinfunction "8_P8") (pintype "passive"))
      (node (ref "X3") (pin "P3") (pinfunction "3_P3") (pintype "passive"))
      (node (ref "X4") (pin "P$5") (pinfunction "5_P$5") (pintype "bidirectional"))
      (node (ref "Y1") (pin "P$2") (pinfunction "GND_P$2") (pintype "passive"))
    )
    (net (code "18") (name "IN00") (class "Default")
      (node (ref "IC15") (pin "4") (pinfunction "PB0/ADC8/AREF_4") (pintype "bidirectional"))
      (node (ref "IC4") (pin "4") (pinfunction "P$4_4") (pintype "bidirectional"))
    )
    (net (code "19") (name "MS1") (class "Default")
      (node (ref "IC15") (pin "42") (pinfunction "PA2/ADC2_42") (pintype "bidirectional"))
      (node (ref "IC2.") (pin "9") (pinfunction "MS1_9") (pintype "input"))
      (node (ref "IC6") (pin "4") (pinfunction "P$4_4") (pintype "bidirectional"))
      (node (ref "R23") (pin "2") (pinfunction "2_2") (pintype "passive"))
    )
    (net (code "20") (name "MS1_IN") (class "Default")
      (node (ref "IC6") (pin "2") (pinfunction "P$2_2") (pintype "bidirectional"))
      (node (ref "R23") (pin "1") (pinfunction "1_1") (pintype "passive"))
      (node (ref "R9") (pin "1") (pinfunction "1_1") (pintype "passive"))
      (node (ref "X2") (pin "P4") (pinfunction "4_P4") (pintype "passive"))
    )
    (net (code "21") (name "MS2") (class "Default")
      (node (ref "IC11") (pin "4") (pinfunction "P$4_4") (pintype "bidirectional"))
      (node (ref "IC15") (pin "43") (pinfunction "PA3/ADC3_43") (pintype "bidirectional"))
      (node (ref "IC2.") (pin "10") (pinfunction "MS2_10") (pintype "input"))
      (node (ref "R24") (pin "2") (pinfunction "2_2") (pintype "passive"))
    )
    (net (code "22") (name "MS2_IN") (class "Default")
      (node (ref "IC11") (pin "2") (pinfunction "P$2_2") (pintype "bidirectional"))
      (node (ref "R12") (pin "1") (pinfunction "1_1") (pintype "passive"))
      (node (ref "R24") (pin "1") (pinfunction "1_1") (pintype "passive"))
      (node (ref "X2") (pin "P5") (pinfunction "5_P5") (pintype "passive"))
    )
    (net (code "23") (name "MS3") (class "Default")
      (node (ref "IC15") (pin "44") (pinfunction "PA4/ADC4_44") (pintype "bidirectional"))
      (node (ref "IC2.") (pin "11") (pinfunction "MS3_11") (pintype "input"))
      (node (ref "IC7") (pin "4") (pinfunction "P$4_4") (pintype "bidirectional"))
      (node (ref "R25") (pin "2") (pinfunction "2_2") (pintype "passive"))
    )
    (net (code "24") (name "MS3_IN") (class "Default")
      (node (ref "IC7") (pin "2") (pinfunction "P$2_2") (pintype "bidirectional"))
      (node (ref "R10") (pin "1") (pinfunction "1_1") (pintype "passive"))
      (node (ref "R25") (pin "1") (pinfunction "1_1") (pintype "passive"))
      (node (ref "X2") (pin "P6") (pinfunction "6_P6") (pintype "passive"))
    )
    (net (code "25") (name "Net-(IC2.-CP1)") (class "Default")
      (node (ref "C2") (pin "2") (pinfunction "2_2") (pintype "passive"))
      (node (ref "IC2.") (pin "4") (pinfunction "CP1_4") (pintype "passive"))
    )
    (net (code "26") (name "Net-(IC2.-CP2)") (class "Default")
      (node (ref "C2") (pin "1") (pinfunction "1_1") (pintype "passive"))
      (node (ref "IC2.") (pin "5") (pinfunction "CP2_5") (pintype "passive"))
    )
    (net (code "27") (name "Net-(IC2.-ROSC)") (class "Default")
      (node (ref "IC2.") (pin "13") (pinfunction "ROSC_13") (pintype "input"))
      (node (ref "R3") (pin "1") (pinfunction "1_1") (pintype "passive"))
    )
    (net (code "28") (name "Net-(IC2.-SENSE1)") (class "Default")
      (node (ref "IC2.") (pin "23") (pinfunction "SENSE1_23") (pintype "input"))
      (node (ref "R2") (pin "1") (pinfunction "1_1") (pintype "passive"))
    )
    (net (code "29") (name "Net-(IC2.-SENSE2)") (class "Default")
      (node (ref "IC2.") (pin "27") (pinfunction "SENSE2_27") (pintype "input"))
      (node (ref "R1") (pin "1") (pinfunction "1_1") (pintype "passive"))
    )
    (net (code "30") (name "Net-(IC2.-VCP)") (class "Default")
      (node (ref "C5") (pin "2") (pinfunction "2_2") (pintype "passive"))
      (node (ref "IC2.") (pin "6") (pinfunction "VCP_6") (pintype "passive"))
    )
    (net (code "31") (name "Net-(IC2.-VREG)") (class "Default")
      (node (ref "C7") (pin "2") (pinfunction "2_2") (pintype "passive"))
      (node (ref "IC2.") (pin "8") (pinfunction "VREG_8") (pintype "passive"))
    )
    (net (code "32") (name "Net-(IC8-P$4)") (class "Default")
      (node (ref "IC8") (pin "4") (pinfunction "P$4_4") (pintype "bidirectional"))
      (node (ref "R15") (pin "1") (pinfunction "1_1") (pintype "passive"))
    )
    (net (code "33") (name "Net-(IC9-P$4)") (class "Default")
      (node (ref "IC9") (pin "4") (pinfunction "P$4_4") (pintype "bidirectional"))
      (node (ref "R16") (pin "1") (pinfunction "1_1") (pintype "passive"))
    )
    (net (code "34") (name "Net-(IC15-PR1{slash}XTAL1)") (class "Default")
      (node (ref "IC15") (pin "37") (pinfunction "PR1/XTAL1_37") (pintype "bidirectional"))
      (node (ref "Y1") (pin "P$3") (pinfunction "OUTPUT_P$3") (pintype "passive"))
    )
    (net (code "35") (name "Net-(IC16-VBUS)") (class "Default")
      (node (ref "C34") (pin "1") (pinfunction "1_1") (pintype "passive"))
      (node (ref "IC16") (pin "P$5") (pinfunction "VBUS_P$5") (pintype "bidirectional"))
      (node (ref "L1") (pin "2") (pinfunction "2_2") (pintype "passive"))
      (node (ref "X4") (pin "P$1") (pinfunction "1_P$1") (pintype "bidirectional"))
    )
    (net (code "36") (name "Net-(IC17-3V3OUT)") (class "Default")
      (node (ref "C39") (pin "1") (pinfunction "1_1") (pintype "passive"))
      (node (ref "IC17") (pin "17") (pinfunction "3V3OUT_17") (pintype "output"))
    )
    (net (code "37") (name "Net-(LED1-PadA)") (class "Default")
      (node (ref "LED1") (pin "A") (pinfunction "A_A") (pintype "bidirectional"))
      (node (ref "LED2") (pin "A") (pinfunction "A_A") (pintype "bidirectional"))
      (node (ref "R17") (pin "1") (pinfunction "1_1") (pintype "passive"))
    )
    (net (code "38") (name "Net-(SW_FA-S)") (class "Default")
      (node (ref "R31") (pin "1") (pinfunction "1_1") (pintype "passive"))
      (node (ref "SW_F") (pin "1") (pinfunction "S_1") (pintype "passive"))
    )
    (net (code "39") (name "Net-(SW_RB-S)") (class "Default")
      (node (ref "R30") (pin "1") (pinfunction "1_1") (pintype "passive"))
      (node (ref "SW_R") (pin "2") (pinfunction "S_2") (pintype "passive"))
    )
    (net (code "40") (name "Net-(X4-2)") (class "Default")
      (node (ref "IC16") (pin "P$1") (pinfunction "IO1_P$1") (pintype "bidirectional"))
      (node (ref "X4") (pin "P$2") (pinfunction "2_P$2") (pintype "bidirectional"))
    )
    (net (code "41") (name "Net-(X4-3)") (class "Default")
      (node (ref "IC16") (pin "P$3") (pinfunction "IO2_P$3") (pintype "bidirectional"))
      (node (ref "X4") (pin "P$3") (pinfunction "3_P$3") (pintype "bidirectional"))
    )
    (net (code "42") (name "Net-(X4-P$1)") (class "Default")
      (node (ref "R18") (pin "1") (pinfunction "1_1") (pintype "passive"))
      (node (ref "X4") (pin "SHIELD_1") (pinfunction "P$1_SHIELD_1") (pintype "bidirectional"))
    )
    (net (code "43") (name "Net-(X4-P$4)") (class "Default")
      (node (ref "C33") (pin "1") (pinfunction "1_1") (pintype "passive"))
      (node (ref "X4") (pin "SHIELD_4") (pinfunction "P$4_SHIELD_4") (pintype "bidirectional"))
    )
    (net (code "44") (name "OUT00") (class "Default")
      (node (ref "IC15") (pin "5") (pinfunction "PB1/ADC9_5") (pintype "bidirectional"))
      (node (ref "IC9") (pin "2") (pinfunction "P$2_2") (pintype "bidirectional"))
      (node (ref "R35") (pin "1") (pinfunction "1_1") (pintype "passive"))
      (node (ref "SJ1") (pin "2") (pinfunction "2_2") (pintype "passive"))
    )
    (net (code "45") (name "OUT01") (class "Default")
      (node (ref "IC15") (pin "6") (pinfunction "PB2/ADC10/DAC0_6") (pintype "bidirectional"))
      (node (ref "IC8") (pin "2") (pinfunction "P$2_2") (pintype "bidirectional"))
      (node (ref "R34") (pin "1") (pinfunction "1_1") (pintype "passive"))
      (node (ref "SJ2") (pin "2") (pinfunction "2_2") (pintype "passive"))
    )
    (net (code "46") (name "OUT1A") (class "Default")
      (node (ref "IC2.") (pin "24") (pinfunction "OUT1A_24") (pintype "output"))
      (node (ref "X1") (pin "2") (pinfunction "S_2") (pintype "passive"))
    )
    (net (code "47") (name "OUT1B") (class "Default")
      (node (ref "IC2.") (pin "21") (pinfunction "OUT1B_21") (pintype "output"))
      (node (ref "X1") (pin "1") (pinfunction "S_1") (pintype "passive"))
    )
    (net (code "48") (name "OUT2A") (class "Default")
      (node (ref "IC2.") (pin "26") (pinfunction "OUT2A_26") (pintype "output"))
      (node (ref "X1") (pin "3") (pinfunction "S_3") (pintype "passive"))
    )
    (net (code "49") (name "OUT2B") (class "Default")
      (node (ref "IC2.") (pin "1") (pinfunction "OUT2B_1") (pintype "output"))
      (node (ref "X1") (pin "4") (pinfunction "S_4") (pintype "passive"))
    )
    (net (code "50") (name "PDI-CLK") (class "Default")
      (node (ref "IC15") (pin "35") (pinfunction "RESET/PDI-CLK_35") (pintype "input"))
      (node (ref "J3") (pin "5") (pinfunction "5_5") (pintype "passive"))
    )
    (net (code "51") (name "PDI-DATA") (class "Default")
      (node (ref "IC15") (pin "34") (pinfunction "PDI-DATA_34") (pintype "bidirectional"))
      (node (ref "J3") (pin "1") (pinfunction "1_1") (pintype "passive"))
    )
    (net (code "52") (name "REF") (class "Default")
      (node (ref "IC2.") (pin "17") (pinfunction "REF_17") (pintype "input"))
      (node (ref "R5") (pin "1") (pinfunction "1_1") (pintype "passive"))
      (node (ref "R6") (pin "1") (pinfunction "1_1") (pintype "passive"))
    )
    (net (code "53") (name "STATE") (class "Default")
      (node (ref "IC15") (pin "36") (pinfunction "PR0/XTAL2_36") (pintype "bidirectional"))
      (node (ref "R17") (pin "2") (pinfunction "2_2") (pintype "passive"))
    )
    (net (code "54") (name "STEP") (class "Default")
      (node (ref "IC15") (pin "40") (pinfunction "PA0/ADC0/AREF_40") (pintype "bidirectional"))
      (node (ref "IC2.") (pin "16") (pinfunction "STEP_16") (pintype "input"))
      (node (ref "IC5") (pin "4") (pinfunction "P$4_4") (pintype "bidirectional"))
      (node (ref "R27") (pin "2") (pinfunction "2_2") (pintype "passive"))
    )
    (net (code "55") (name "STEP_IN") (class "Default")
      (node (ref "IC5") (pin "2") (pinfunction "P$2_2") (pintype "bidirectional"))
      (node (ref "R27") (pin "1") (pinfunction "1_1") (pintype "passive"))
      (node (ref "R8") (pin "1") (pinfunction "1_1") (pintype "passive"))
      (node (ref "X2") (pin "P1") (pinfunction "1_P1") (pintype "passive"))
    )
    (net (code "56") (name "SW_F") (class "Default")
      (node (ref "C42") (pin "1") (pinfunction "1_1") (pintype "passive"))
      (node (ref "IC15") (pin "14") (pinfunction "PC4/OC1A/#SS_14") (pintype "bidirectional"))
      (node (ref "R31") (pin "2") (pinfunction "2_2") (pintype "passive"))
      (node (ref "R32") (pin "1") (pinfunction "1_1") (pintype "passive"))
      (node (ref "SJ1") (pin "1") (pinfunction "1_1") (pintype "passive"))
    )
    (net (code "57") (name "SW_R") (class "Default")
      (node (ref "C41") (pin "1") (pinfunction "1_1") (pintype "passive"))
      (node (ref "IC15") (pin "15") (pinfunction "PC5/OC1B/MOSI/XCK1_15") (pintype "bidirectional"))
      (node (ref "R30") (pin "2") (pinfunction "2_2") (pintype "passive"))
      (node (ref "R33") (pin "2") (pinfunction "2_2") (pintype "passive"))
      (node (ref "SJ2") (pin "1") (pinfunction "1_1") (pintype "passive"))
    )
    (net (code "58") (name "USB5V") (class "Default")
      (node (ref "C37") (pin "1") (pinfunction "1_1") (pintype "passive"))
      (node (ref "C38") (pin "+") (pinfunction "+_+") (pintype "passive"))
      (node (ref "C40") (pin "1") (pinfunction "1_1") (pintype "passive"))
      (node (ref "IC17") (pin "20") (pinfunction "VCC_20") (pintype "power_in"))
      (node (ref "IC17") (pin "4") (pinfunction "VCCIO_4") (pintype "power_in"))
      (node (ref "L1") (pin "1") (pinfunction "1_1") (pintype "passive"))
    )
    (net (code "59") (name "USBDM") (class "Default")
      (node (ref "C36") (pin "1") (pinfunction "1_1") (pintype "passive"))
      (node (ref "IC16") (pin "P$6") (pinfunction "IO1_P$6") (pintype "bidirectional"))
      (node (ref "IC17") (pin "16") (pinfunction "USBDM_16") (pintype "bidirectional"))
    )
    (net (code "60") (name "USBDP") (class "Default")
      (node (ref "C35") (pin "1") (pinfunction "1_1") (pintype "passive"))
      (node (ref "IC16") (pin "P$4") (pinfunction "IO2_P$4") (pintype "bidirectional"))
      (node (ref "IC17") (pin "15") (pinfunction "USBDP_15") (pintype "bidirectional"))
    )
    (net (code "61") (name "VCCINT") (class "Default")
      (node (ref "C13") (pin "1") (pinfunction "1_1") (pintype "passive"))
      (node (ref "C14") (pin "1") (pinfunction "1_1") (pintype "passive"))
      (node (ref "C15") (pin "1") (pinfunction "1_1") (pintype "passive"))
      (node (ref "C16") (pin "1") (pinfunction "1_1") (pintype "passive"))
      (node (ref "C19") (pin "1") (pinfunction "1_1") (pintype "passive"))
      (node (ref "C20") (pin "1") (pinfunction "1_1") (pintype "passive"))
      (node (ref "C21") (pin "1") (pinfunction "1_1") (pintype "passive"))
      (node (ref "C25") (pin "1") (pinfunction "1_1") (pintype "passive"))
      (node (ref "IC10") (pin "5") (pinfunction "P$5_5") (pintype "bidirectional"))
      (node (ref "IC11") (pin "5") (pinfunction "P$5_5") (pintype "bidirectional"))
      (node (ref "IC12") (pin "5") (pinfunction "P$5_5") (pintype "bidirectional"))
      (node (ref "IC13") (pin "5") (pinfunction "OUT_5") (pintype "bidirectional"))
      (node (ref "IC4") (pin "5") (pinfunction "P$5_5") (pintype "bidirectional"))
      (node (ref "IC5") (pin "5") (pinfunction "P$5_5") (pintype "bidirectional"))
      (node (ref "IC6") (pin "5") (pinfunction "P$5_5") (pintype "bidirectional"))
      (node (ref "IC7") (pin "5") (pinfunction "P$5_5") (pintype "bidirectional"))
      (node (ref "JP1") (pin "3") (pinfunction "3_3") (pintype "passive"))
      (node (ref "R14") (pin "1") (pinfunction "1_1") (pintype "passive"))
    )
    (net (code "62") (name "VCCIO") (class "Default")
      (node (ref "C22") (pin "1") (pinfunction "1_1") (pintype "passive"))
      (node (ref "C26") (pin "1") (pinfunction "1_1") (pintype "passive"))
      (node (ref "C27") (pin "1") (pinfunction "1_1") (pintype "passive"))
      (node (ref "C28") (pin "1") (pinfunction "1_1") (pintype "passive"))
      (node (ref "C29") (pin "1") (pinfunction "1_1") (pintype "passive"))
      (node (ref "C30") (pin "1") (pinfunction "1_1") (pintype "passive"))
      (node (ref "C31") (pin "1") (pinfunction "1_1") (pintype "passive"))
      (node (ref "C32") (pin "1") (pinfunction "1_1") (pintype "passive"))
      (node (ref "IC14") (pin "5") (pinfunction "OUT_5") (pintype "bidirectional"))
      (node (ref "IC15") (pin "19") (pinfunction "VCC_19") (pintype "power_in"))
      (node (ref "IC15") (pin "31") (pinfunction "VCC_31") (pintype "power_in"))
      (node (ref "IC15") (pin "39") (pinfunction "AVCC_39") (pintype "power_in"))
      (node (ref "IC15") (pin "9") (pinfunction "VCC_9") (pintype "power_in"))
      (node (ref "J2") (pin "1") (pinfunction "1_1") (pintype "passive"))
      (node (ref "J3") (pin "2") (pinfunction "2_2") (pintype "passive"))
      (node (ref "R19") (pin "2") (pinfunction "2_2") (pintype "passive"))
      (node (ref "R20") (pin "2") (pinfunction "2_2") (pintype "passive"))
      (node (ref "R21") (pin "2") (pinfunction "2_2") (pintype "passive"))
      (node (ref "R32") (pin "2") (pinfunction "2_2") (pintype "passive"))
      (node (ref "R33") (pin "1") (pinfunction "1_1") (pintype "passive"))
      (node (ref "SJ4") (pin "2") (pinfunction "2_2") (pintype "passive"))
      (node (ref "Y1") (pin "P$4") (pinfunction "VDD_P$4") (pintype "passive"))
    )
    (net (code "63") (name "VDD_M") (class "Default")
      (node (ref "C10") (pin "2") (pinfunction "2_2") (pintype "passive"))
      (node (ref "C12") (pin "1") (pinfunction "1_1") (pintype "passive"))
      (node (ref "IC2.") (pin "15") (pinfunction "VDD_15") (pintype "power_in"))
      (node (ref "IC3") (pin "5") (pinfunction "OUT_5") (pintype "bidirectional"))
      (node (ref "R22") (pin "2") (pinfunction "2_2") (pintype "passive"))
      (node (ref "R4") (pin "2") (pinfunction "2_2") (pintype "passive"))
      (node (ref "R5") (pin "2") (pinfunction "2_2") (pintype "passive"))
      (node (ref "SJ3") (pin "2") (pinfunction "2_2") (pintype "passive"))
    )
    (net (code "64") (name "unconnected-(IC2.-NC-Pad7)") (class "Default")
      (node (ref "IC2.") (pin "7") (pinfunction "NC_7") (pintype "no_connect"))
    )
    (net (code "65") (name "unconnected-(IC2.-NC-Pad20)") (class "Default")
      (node (ref "IC2.") (pin "20") (pinfunction "NC_20") (pintype "no_connect"))
    )
    (net (code "66") (name "unconnected-(IC2.-NC-Pad25)") (class "Default")
      (node (ref "IC2.") (pin "25") (pinfunction "NC_25") (pintype "no_connect"))
    )
    (net (code "67") (name "unconnected-(IC3-N{slash}C-Pad4)") (class "Default")
      (node (ref "IC3") (pin "4") (pinfunction "N/C_4") (pintype "bidirectional"))
    )
    (net (code "68") (name "unconnected-(IC13-N{slash}C-Pad4)") (class "Default")
      (node (ref "IC13") (pin "4") (pinfunction "N/C_4") (pintype "bidirectional"))
    )
    (net (code "69") (name "unconnected-(IC14-N{slash}C-Pad4)") (class "Default")
      (node (ref "IC14") (pin "4") (pinfunction "N/C_4") (pintype "bidirectional"))
    )
    (net (code "70") (name "unconnected-(IC15-PC0{slash}OC0A{slash}SDA-Pad10)") (class "Default")
      (node (ref "IC15") (pin "10") (pinfunction "PC0/OC0A/SDA_10") (pintype "bidirectional"))
    )
    (net (code "71") (name "unconnected-(IC15-PC1{slash}OC0B{slash}XCK0{slash}SCL-Pad11)") (class "Default")
      (node (ref "IC15") (pin "11") (pinfunction "PC1/OC0B/XCK0/SCL_11") (pintype "bidirectional"))
    )
    (net (code "72") (name "unconnected-(IC15-PC3{slash}OC0D{slash}TXD0-Pad13)") (class "Default")
      (node (ref "IC15") (pin "13") (pinfunction "PC3/OC0D/TXD0_13") (pintype "bidirectional"))
    )
    (net (code "73") (name "unconnected-(IC15-PC6{slash}MISO{slash}RXD1-Pad16)") (class "Default")
      (node (ref "IC15") (pin "16") (pinfunction "PC6/MISO/RXD1_16") (pintype "bidirectional"))
    )
    (net (code "74") (name "unconnected-(IC15-PC7{slash}SCK{slash}TXD1{slash}CLKO{slash}EVO-Pad17)") (class "Default")
      (node (ref "IC15") (pin "17") (pinfunction "PC7/SCK/TXD1/CLKO/EVO_17") (pintype "bidirectional"))
    )
    (net (code "75") (name "unconnected-(IC15-~OC0BXCK0PD1-Pad21)") (class "Default")
      (node (ref "IC15") (pin "21") (pinfunction "~OC0BXCK0PD1_21") (pintype "bidirectional"))
    )
    (net (code "76") (name "unconnected-(IC15-~OC0CRXD0PD2-Pad22)") (class "Default")
      (node (ref "IC15") (pin "22") (pinfunction "~OC0CRXD0PD2_22") (pintype "bidirectional"))
    )
    (net (code "77") (name "unconnected-(IC15-~OC0DTXD0PD3-Pad23)") (class "Default")
      (node (ref "IC15") (pin "23") (pinfunction "~OC0DTXD0PD3_23") (pintype "bidirectional"))
    )
    (net (code "78") (name "unconnected-(IC15-~{#SSPD4}-Pad24)") (class "Default")
      (node (ref "IC15") (pin "24") (pinfunction "~{#SSPD4}_24") (pintype "bidirectional"))
    )
    (net (code "79") (name "unconnected-(IC17-CBUS0-Pad23)") (class "Default")
      (node (ref "IC17") (pin "23") (pinfunction "CBUS0_23") (pintype "bidirectional"))
    )
    (net (code "80") (name "unconnected-(IC17-CBUS1-Pad22)") (class "Default")
      (node (ref "IC17") (pin "22") (pinfunction "CBUS1_22") (pintype "bidirectional"))
    )
    (net (code "81") (name "unconnected-(IC17-CBUS2-Pad13)") (class "Default")
      (node (ref "IC17") (pin "13") (pinfunction "CBUS2_13") (pintype "bidirectional"))
    )
    (net (code "82") (name "unconnected-(IC17-CBUS3-Pad14)") (class "Default")
      (node (ref "IC17") (pin "14") (pinfunction "CBUS3_14") (pintype "bidirectional"))
    )
    (net (code "83") (name "unconnected-(IC17-CBUS4-Pad12)") (class "Default")
      (node (ref "IC17") (pin "12") (pinfunction "CBUS4_12") (pintype "bidirectional"))
    )
    (net (code "84") (name "unconnected-(IC17-OSCI-Pad27)") (class "Default")
      (node (ref "IC17") (pin "27") (pinfunction "OSCI_27") (pintype "input"))
    )
    (net (code "85") (name "unconnected-(IC17-OSCO-Pad28)") (class "Default")
      (node (ref "IC17") (pin "28") (pinfunction "OSCO_28") (pintype "output"))
    )
    (net (code "86") (name "unconnected-(IC17-~{DCD}-Pad10)") (class "Default")
      (node (ref "IC17") (pin "10") (pinfunction "~{DCD}_10") (pintype "input"))
    )
    (net (code "87") (name "unconnected-(IC17-~{DSR}-Pad9)") (class "Default")
      (node (ref "IC17") (pin "9") (pinfunction "~{DSR}_9") (pintype "input"))
    )
    (net (code "88") (name "unconnected-(IC17-~{DTR}-Pad2)") (class "Default")
      (node (ref "IC17") (pin "2") (pinfunction "~{DTR}_2") (pintype "output"))
    )
    (net (code "89") (name "unconnected-(IC17-~{RESET}-Pad19)") (class "Default")
      (node (ref "IC17") (pin "19") (pinfunction "~{RESET}_19") (pintype "input"))
    )
    (net (code "90") (name "unconnected-(IC17-~{RI}-Pad6)") (class "Default")
      (node (ref "IC17") (pin "6") (pinfunction "~{RI}_6") (pintype "input"))
    )
    (net (code "91") (name "unconnected-(J3-Pad3)") (class "Default")
      (node (ref "J3") (pin "3") (pinfunction "3_3") (pintype "passive"))
    )
    (net (code "92") (name "unconnected-(J3-Pad4)") (class "Default")
      (node (ref "J3") (pin "4") (pinfunction "4_4") (pintype "passive"))
    )
    (net (code "93") (name "unconnected-(SW3-PadO1)") (class "Default")
      (node (ref "SW3") (pin "O1") (pinfunction "O1_O1") (pintype "passive"))
    )
    (net (code "94") (name "unconnected-(SW3-PadP1)") (class "Default")
      (node (ref "SW3") (pin "P1") (pinfunction "P1_P1") (pintype "passive"))
    )
    (net (code "95") (name "unconnected-(X4-4-PadP$4)") (class "Default")
      (node (ref "X4") (pin "P$4") (pinfunction "4_P$4") (pintype "bidirectional"))
    )
    (net (code "96") (name "unconnected-(X4-P$2-PadSHIELD_2)") (class "Default")
      (node (ref "X4") (pin "SHIELD_2") (pinfunction "P$2_SHIELD_2") (pintype "bidirectional"))
    )
    (net (code "97") (name "unconnected-(X4-P$3-PadSHIELD_3)") (class "Default")
      (node (ref "X4") (pin "SHIELD_3") (pinfunction "P$3_SHIELD_3") (pintype "bidirectional"))
    )
    (net (code "98") (name "unconnected-(Y1-STANDBY#-PadP$1)") (class "Default")
      (node (ref "Y1") (pin "P$1") (pinfunction "STANDBY#_P$1") (pintype "passive"))
    )
    (net (code "99") (name "~{BUF_EN}") (class "Default")
      (node (ref "IC10") (pin "1") (pinfunction "P$1_1") (pintype "bidirectional"))
      (node (ref "IC11") (pin "1") (pinfunction "P$1_1") (pintype "bidirectional"))
      (node (ref "IC15") (pin "7") (pinfunction "PB3/ADC11/DAC1_7") (pintype "bidirectional"))
      (node (ref "IC5") (pin "1") (pinfunction "P$1_1") (pintype "bidirectional"))
      (node (ref "IC6") (pin "1") (pinfunction "P$1_1") (pintype "bidirectional"))
      (node (ref "IC7") (pin "1") (pinfunction "P$1_1") (pintype "bidirectional"))
      (node (ref "R14") (pin "2") (pinfunction "2_2") (pintype "passive"))
    )
    (net (code "100") (name "~{EN_DRIVER_IN}") (class "Default")
      (node (ref "IC12") (pin "2") (pinfunction "P$2_2") (pintype "bidirectional"))
      (node (ref "R13") (pin "1") (pinfunction "1_1") (pintype "passive"))
      (node (ref "R28") (pin "1") (pinfunction "1_1") (pintype "passive"))
      (node (ref "R29") (pin "1") (pinfunction "1_1") (pintype "passive"))
      (node (ref "X2") (pin "P7") (pinfunction "7_P7") (pintype "passive"))
    )
    (net (code "101") (name "~{EN_DRIVER_UC}") (class "Default")
      (node (ref "IC12") (pin "4") (pinfunction "P$4_4") (pintype "bidirectional"))
      (node (ref "IC15") (pin "20") (pinfunction "~{OC0APD0}_20") (pintype "bidirectional"))
    )
    (net (code "102") (name "~{EN_DRIVER}") (class "Default")
      (node (ref "IC15") (pin "1") (pinfunction "PA5/ADC5_1") (pintype "bidirectional"))
      (node (ref "IC2.") (pin "2") (pinfunction "ENABLE_2") (pintype "input"))
      (node (ref "R28") (pin "2") (pinfunction "2_2") (pintype "passive"))
    )
    (net (code "103") (name "~{RESET}") (class "Default")
      (node (ref "IC15") (pin "3") (pinfunction "PA7/ADC7/AC0-OUT_3") (pintype "bidirectional"))
      (node (ref "IC2.") (pin "12") (pinfunction "RESET_12") (pintype "input"))
      (node (ref "R22") (pin "1") (pinfunction "1_1") (pintype "passive"))
    )
    (net (code "104") (name "~{SLEEP}") (class "Default")
      (node (ref "IC15") (pin "2") (pinfunction "PA6/ADC6_2") (pintype "bidirectional"))
      (node (ref "IC2.") (pin "14") (pinfunction "SLEEP_14") (pintype "input"))
      (node (ref "R4") (pin "1") (pinfunction "1_1") (pintype "passive"))
    )
  )
)
